# sensorTensao_Corrente_rev1_0.net
KiCad netlist of a schematic drawn in EAGLE
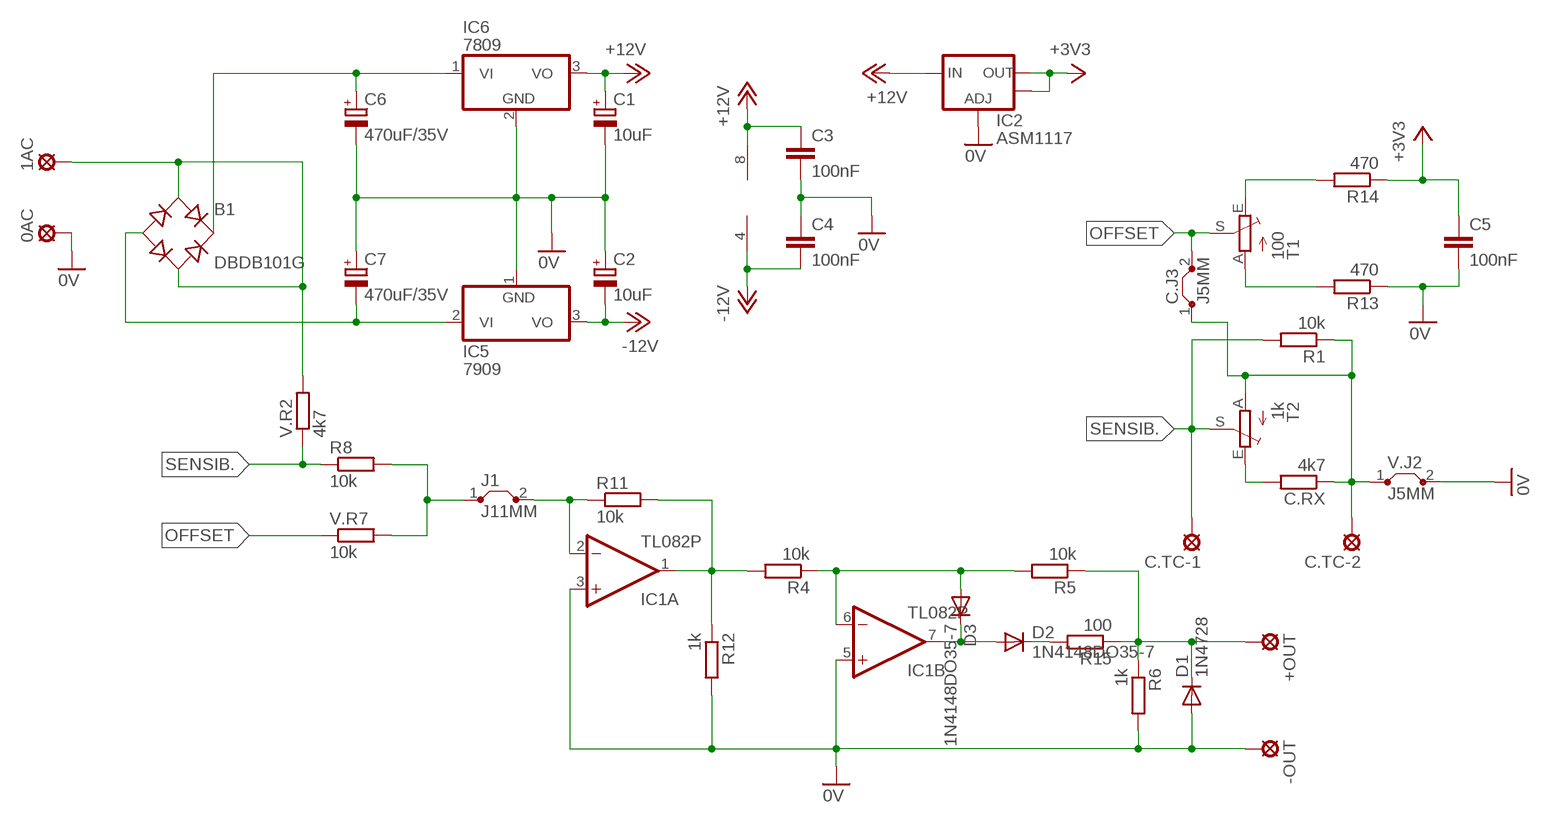
[diagram p0: schematic, sheet 1]

(export (version "E")
  (design (tool "Eeschema 10.0.6"))
  (components
    (comp (ref "+OUT")
      (value "+D")
      (footprint "eagle-import:LSP10")
      (libsource (lib "eagle-import") (part "LSP10"))
    )
    (comp (ref "-OUT")
      (value "0V")
      (footprint "eagle-import:LSP10")
      (libsource (lib "eagle-import") (part "LSP10"))
    )
    (comp (ref "0AC")
      (value "0V")
      (footprint "eagle-import:LSP10")
      (libsource (lib "eagle-import") (part "LSP10"))
    )
    (comp (ref "1AC")
      (value "AC")
      (footprint "eagle-import:LSP10")
      (libsource (lib "eagle-import") (part "LSP10"))
    )
    (comp (ref "B1")
      (value "DBDB101G")
      (footprint "eagle-import:DB")
      (libsource (lib "eagle-import") (part "DB?GDB101"))
    )
    (comp (ref "C.J3")
      (value "J5MM")
      (footprint "eagle-import:05")
      (libsource (lib "eagle-import") (part "J5MM"))
    )
    (comp (ref "C.RX")
      (value "4k7")
      (footprint "eagle-import:0204_7")
      (libsource (lib "eagle-import") (part "R-EU_0204/7"))
    )
    (comp (ref "C.TC-1")
      (value "0V")
      (footprint "eagle-import:LSP10")
      (libsource (lib "eagle-import") (part "LSP10"))
    )
    (comp (ref "C.TC-2")
      (value "0V")
      (footprint "eagle-import:LSP10")
      (libsource (lib "eagle-import") (part "LSP10"))
    )
    (comp (ref "C1")
      (value "10uF")
      (footprint "eagle-import:E2,5-7")
      (libsource (lib "eagle-import") (part "CPOL-EUE2.5-7"))
    )
    (comp (ref "C2")
      (value "10uF")
      (footprint "eagle-import:E2,5-7")
      (libsource (lib "eagle-import") (part "CPOL-EUE2.5-7"))
    )
    (comp (ref "C3")
      (value "100nF")
      (footprint "eagle-import:C050-024X044")
      (libsource (lib "eagle-import") (part "C-EU050-024X044"))
    )
    (comp (ref "C4")
      (value "100nF")
      (footprint "eagle-import:C050-024X044")
      (libsource (lib "eagle-import") (part "C-EU050-024X044"))
    )
    (comp (ref "C5")
      (value "100nF")
      (footprint "eagle-import:C050-024X044")
      (libsource (lib "eagle-import") (part "C-EU050-024X044"))
    )
    (comp (ref "C6")
      (value "470uF/35V")
      (footprint "eagle-import:E3,5-10")
      (libsource (lib "eagle-import") (part "CPOL-EUE3.5-10"))
    )
    (comp (ref "C7")
      (value "470uF/35V")
      (footprint "eagle-import:E3,5-10")
      (libsource (lib "eagle-import") (part "CPOL-EUE3.5-10"))
    )
    (comp (ref "D1")
      (value "1N4728")
      (footprint "eagle-import:DO35-7")
      (libsource (lib "eagle-import") (part "1N4148DO35-7"))
    )
    (comp (ref "D2")
      (value "1N4148DO35-7")
      (footprint "eagle-import:DO35-7")
      (libsource (lib "eagle-import") (part "1N4148DO35-7"))
    )
    (comp (ref "D3")
      (value "1N4148DO35-7")
      (footprint "eagle-import:DO35-7")
      (libsource (lib "eagle-import") (part "1N4148DO35-7"))
    )
    (comp (ref "IC1")
      (value "TL082P")
      (footprint "eagle-import:DIL08")
      (libsource (lib "eagle-import") (part "TL082P"))
    )
    (comp (ref "IC2")
      (value "ASM1117")
      (footprint "eagle-import:SOT223")
      (libsource (lib "eagle-import") (part "V_REG_LM1117SOT223"))
    )
    (comp (ref "IC5")
      (value "7909")
      (footprint "eagle-import:TO220V")
      (libsource (lib "eagle-import") (part "7912"))
    )
    (comp (ref "IC6")
      (value "7809")
      (footprint "eagle-import:TO220V")
      (libsource (lib "eagle-import") (part "78TV12"))
    )
    (comp (ref "J1")
      (value "J11MM")
      (footprint "eagle-import:11")
      (libsource (lib "eagle-import") (part "jumper_252_J11MM"))
    )
    (comp (ref "R1")
      (value "10k")
      (footprint "eagle-import:0204_7")
      (libsource (lib "eagle-import") (part "R-EU_0204/7"))
    )
    (comp (ref "R4")
      (value "10k")
      (footprint "eagle-import:0204_7")
      (libsource (lib "eagle-import") (part "R-EU_0204/7"))
    )
    (comp (ref "R5")
      (value "10k")
      (footprint "eagle-import:0204_10")
      (libsource (lib "eagle-import") (part "R-EU_0204/10"))
    )
    (comp (ref "R6")
      (value "1k")
      (footprint "eagle-import:0204_7")
      (libsource (lib "eagle-import") (part "R-EU_0204/7"))
    )
    (comp (ref "R8")
      (value "10k")
      (footprint "eagle-import:0204_7")
      (libsource (lib "eagle-import") (part "R-EU_0204/7"))
    )
    (comp (ref "R11")
      (value "10k")
      (footprint "eagle-import:0204_7")
      (libsource (lib "eagle-import") (part "R-EU_0204/7"))
    )
    (comp (ref "R12")
      (value "1k")
      (footprint "eagle-import:0204_7")
      (libsource (lib "eagle-import") (part "R-EU_0204/7"))
    )
    (comp (ref "R13")
      (value "470")
      (footprint "eagle-import:0204_7")
      (libsource (lib "eagle-import") (part "R-EU_0204/7"))
    )
    (comp (ref "R14")
      (value "470")
      (footprint "eagle-import:0204_7")
      (libsource (lib "eagle-import") (part "R-EU_0204/7"))
    )
    (comp (ref "R15")
      (value "100")
      (footprint "eagle-import:0204_7")
      (libsource (lib "eagle-import") (part "R-EU_0204/7"))
    )
    (comp (ref "T1")
      (value "100")
      (footprint "eagle-import:CA6V")
      (libsource (lib "eagle-import") (part "TRIM_EU-CA6V"))
    )
    (comp (ref "T2")
      (value "1k")
      (footprint "eagle-import:CA6V")
      (libsource (lib "eagle-import") (part "TRIM_EU-CA6V"))
    )
    (comp (ref "V.J2")
      (value "J5MM")
      (footprint "eagle-import:05")
      (libsource (lib "eagle-import") (part "J5MM"))
    )
    (comp (ref "V.R2")
      (value "4k7")
      (footprint "eagle-import:0204_7")
      (libsource (lib "eagle-import") (part "R-EU_0204/7"))
    )
    (comp (ref "V.R7")
      (value "10k")
      (footprint "eagle-import:0204_7")
      (libsource (lib "eagle-import") (part "R-EU_0204/7"))
    )
  )
  (nets
    (net (code "1") (name "+3V3") (class "Default")
      (node (ref "C5") (pin "1") (pinfunction "1_1") (pintype "passive"))
      (node (ref "IC2") (pin "2") (pinfunction "OUT_2") (pintype "output"))
      (node (ref "IC2") (pin "4") (pinfunction "OUT_4") (pintype "output"))
      (node (ref "R14") (pin "1") (pinfunction "1_1") (pintype "passive"))
    )
    (net (code "2") (name "+12V") (class "Default")
      (node (ref "C1") (pin "+") (pinfunction "+_+") (pintype "passive"))
      (node (ref "C3") (pin "1") (pinfunction "1_1") (pintype "passive"))
      (node (ref "IC1") (pin "8") (pinfunction "V+_8") (pintype "power_in"))
      (node (ref "IC2") (pin "3") (pinfunction "IN_3") (pintype "input"))
      (node (ref "IC6") (pin "3") (pinfunction "VO_3") (pintype "passive"))
    )
    (net (code "3") (name "-12V") (class "Default")
      (node (ref "C2") (pin "-") (pinfunction "-_-") (pintype "passive"))
      (node (ref "C4") (pin "2") (pinfunction "2_2") (pintype "passive"))
      (node (ref "IC1") (pin "4") (pinfunction "V-_4") (pintype "power_in"))
      (node (ref "IC5") (pin "3") (pinfunction "VO_3") (pintype "passive"))
    )
    (net (code "4") (name "0V") (class "Default")
      (node (ref "-OUT") (pin "MP") (pinfunction "MP_MP") (pintype "passive"))
      (node (ref "0AC") (pin "MP") (pinfunction "MP_MP") (pintype "passive"))
      (node (ref "C1") (pin "-") (pinfunction "-_-") (pintype "passive"))
      (node (ref "C2") (pin "+") (pinfunction "+_+") (pintype "passive"))
      (node (ref "C3") (pin "2") (pinfunction "2_2") (pintype "passive"))
      (node (ref "C4") (pin "1") (pinfunction "1_1") (pintype "passive"))
      (node (ref "C5") (pin "2") (pinfunction "2_2") (pintype "passive"))
      (node (ref "C6") (pin "-") (pinfunction "-_-") (pintype "passive"))
      (node (ref "C7") (pin "+") (pinfunction "+_+") (pintype "passive"))
      (node (ref "D1") (pin "A") (pinfunction "A_A") (pintype "passive"))
      (node (ref "IC1") (pin "3") (pinfunction "+IN_3") (pintype "input"))
      (node (ref "IC1") (pin "5") (pinfunction "+IN_5") (pintype "input"))
      (node (ref "IC2") (pin "1") (pinfunction "ADJ_1") (pintype "input"))
      (node (ref "IC5") (pin "1") (pinfunction "GND_1") (pintype "passive"))
      (node (ref "IC6") (pin "2") (pinfunction "GND_2") (pintype "passive"))
      (node (ref "R12") (pin "2") (pinfunction "2_2") (pintype "passive"))
      (node (ref "R13") (pin "1") (pinfunction "1_1") (pintype "passive"))
      (node (ref "R6") (pin "2") (pinfunction "2_2") (pintype "passive"))
      (node (ref "V.J2") (pin "2") (pinfunction "2_2") (pintype "passive"))
    )
    (net (code "5") (name "Net-(+OUT-PadMP)") (class "Default")
      (node (ref "+OUT") (pin "MP") (pinfunction "MP_MP") (pintype "passive"))
      (node (ref "D1") (pin "C") (pinfunction "C_C") (pintype "passive"))
      (node (ref "R15") (pin "1") (pinfunction "1_1") (pintype "passive"))
      (node (ref "R5") (pin "1") (pinfunction "1_1") (pintype "passive"))
      (node (ref "R6") (pin "1") (pinfunction "1_1") (pintype "passive"))
    )
    (net (code "6") (name "Net-(1AC-PadMP)") (class "Default")
      (node (ref "1AC") (pin "MP") (pinfunction "MP_MP") (pintype "passive"))
      (node (ref "B1") (pin "AC1") (pinfunction "AC1_AC1") (pintype "passive"))
      (node (ref "B1") (pin "AC2") (pinfunction "AC2_AC2") (pintype "passive"))
      (node (ref "V.R2") (pin "2") (pinfunction "2_2") (pintype "passive"))
    )
    (net (code "7") (name "Net-(C.J3-Pad1)") (class "Default")
      (node (ref "C.J3") (pin "1") (pinfunction "1_1") (pintype "passive"))
      (node (ref "C.RX") (pin "1") (pinfunction "1_1") (pintype "passive"))
      (node (ref "C.TC-2") (pin "MP") (pinfunction "MP_MP") (pintype "passive"))
      (node (ref "R1") (pin "1") (pinfunction "1_1") (pintype "passive"))
      (node (ref "T2") (pin "A") (pinfunction "A_A") (pintype "passive"))
      (node (ref "V.J2") (pin "1") (pinfunction "1_1") (pintype "passive"))
    )
    (net (code "8") (name "Net-(C.RX-Pad2)") (class "Default")
      (node (ref "C.RX") (pin "2") (pinfunction "2_2") (pintype "passive"))
      (node (ref "T2") (pin "E") (pinfunction "E_E") (pintype "passive"))
    )
    (net (code "9") (name "Net-(D2-PadC)") (class "Default")
      (node (ref "D2") (pin "C") (pinfunction "C_C") (pintype "passive"))
      (node (ref "R15") (pin "2") (pinfunction "2_2") (pintype "passive"))
    )
    (net (code "10") (name "Net-(IC1A--IN)") (class "Default")
      (node (ref "IC1") (pin "2") (pinfunction "-IN_2") (pintype "input"))
      (node (ref "J1") (pin "2") (pinfunction "2_2") (pintype "passive"))
      (node (ref "R11") (pin "1") (pinfunction "1_1") (pintype "passive"))
    )
    (net (code "11") (name "Net-(IC1A-OUT)") (class "Default")
      (node (ref "IC1") (pin "1") (pinfunction "OUT_1") (pintype "output"))
      (node (ref "R11") (pin "2") (pinfunction "2_2") (pintype "passive"))
      (node (ref "R12") (pin "1") (pinfunction "1_1") (pintype "passive"))
      (node (ref "R4") (pin "2") (pinfunction "2_2") (pintype "passive"))
    )
    (net (code "12") (name "Net-(IC1B--IN)") (class "Default")
      (node (ref "D3") (pin "A") (pinfunction "A_A") (pintype "passive"))
      (node (ref "IC1") (pin "6") (pinfunction "-IN_6") (pintype "input"))
      (node (ref "R4") (pin "1") (pinfunction "1_1") (pintype "passive"))
      (node (ref "R5") (pin "2") (pinfunction "2_2") (pintype "passive"))
    )
    (net (code "13") (name "Net-(IC1B-OUT)") (class "Default")
      (node (ref "D2") (pin "A") (pinfunction "A_A") (pintype "passive"))
      (node (ref "D3") (pin "C") (pinfunction "C_C") (pintype "passive"))
      (node (ref "IC1") (pin "7") (pinfunction "OUT_7") (pintype "output"))
    )
    (net (code "14") (name "Net-(IC5-VI)") (class "Default")
      (node (ref "B1") (pin "-") (pinfunction "-_-") (pintype "passive"))
      (node (ref "C7") (pin "-") (pinfunction "-_-") (pintype "passive"))
      (node (ref "IC5") (pin "2") (pinfunction "VI_2") (pintype "input"))
    )
    (net (code "15") (name "Net-(IC6-VI)") (class "Default")
      (node (ref "B1") (pin "+") (pinfunction "+_+") (pintype "passive"))
      (node (ref "C6") (pin "+") (pinfunction "+_+") (pintype "passive"))
      (node (ref "IC6") (pin "1") (pinfunction "VI_1") (pintype "input"))
    )
    (net (code "16") (name "Net-(J1-Pad1)") (class "Default")
      (node (ref "J1") (pin "1") (pinfunction "1_1") (pintype "passive"))
      (node (ref "R8") (pin "2") (pinfunction "2_2") (pintype "passive"))
      (node (ref "V.R7") (pin "2") (pinfunction "2_2") (pintype "passive"))
    )
    (net (code "17") (name "Net-(R13-Pad2)") (class "Default")
      (node (ref "R13") (pin "2") (pinfunction "2_2") (pintype "passive"))
      (node (ref "T1") (pin "A") (pinfunction "A_A") (pintype "passive"))
    )
    (net (code "18") (name "Net-(R14-Pad2)") (class "Default")
      (node (ref "R14") (pin "2") (pinfunction "2_2") (pintype "passive"))
      (node (ref "T1") (pin "E") (pinfunction "E_E") (pintype "passive"))
    )
    (net (code "19") (name "OFFSET") (class "Default")
      (node (ref "C.J3") (pin "2") (pinfunction "2_2") (pintype "passive"))
      (node (ref "T1") (pin "S") (pinfunction "S_S") (pintype "passive"))
      (node (ref "V.R7") (pin "1") (pinfunction "1_1") (pintype "passive"))
    )
    (net (code "20") (name "SENSIB.") (class "Default")
      (node (ref "C.TC-1") (pin "MP") (pinfunction "MP_MP") (pintype "passive"))
      (node (ref "R1") (pin "2") (pinfunction "2_2") (pintype "passive"))
      (node (ref "R8") (pin "1") (pinfunction "1_1") (pintype "passive"))
      (node (ref "T2") (pin "S") (pinfunction "S_S") (pintype "passive"))
      (node (ref "V.R2") (pin "1") (pinfunction "1_1") (pintype "passive"))
    )
  )
)
